# IMU.net
KiCad netlist of a schematic drawn in EAGLE
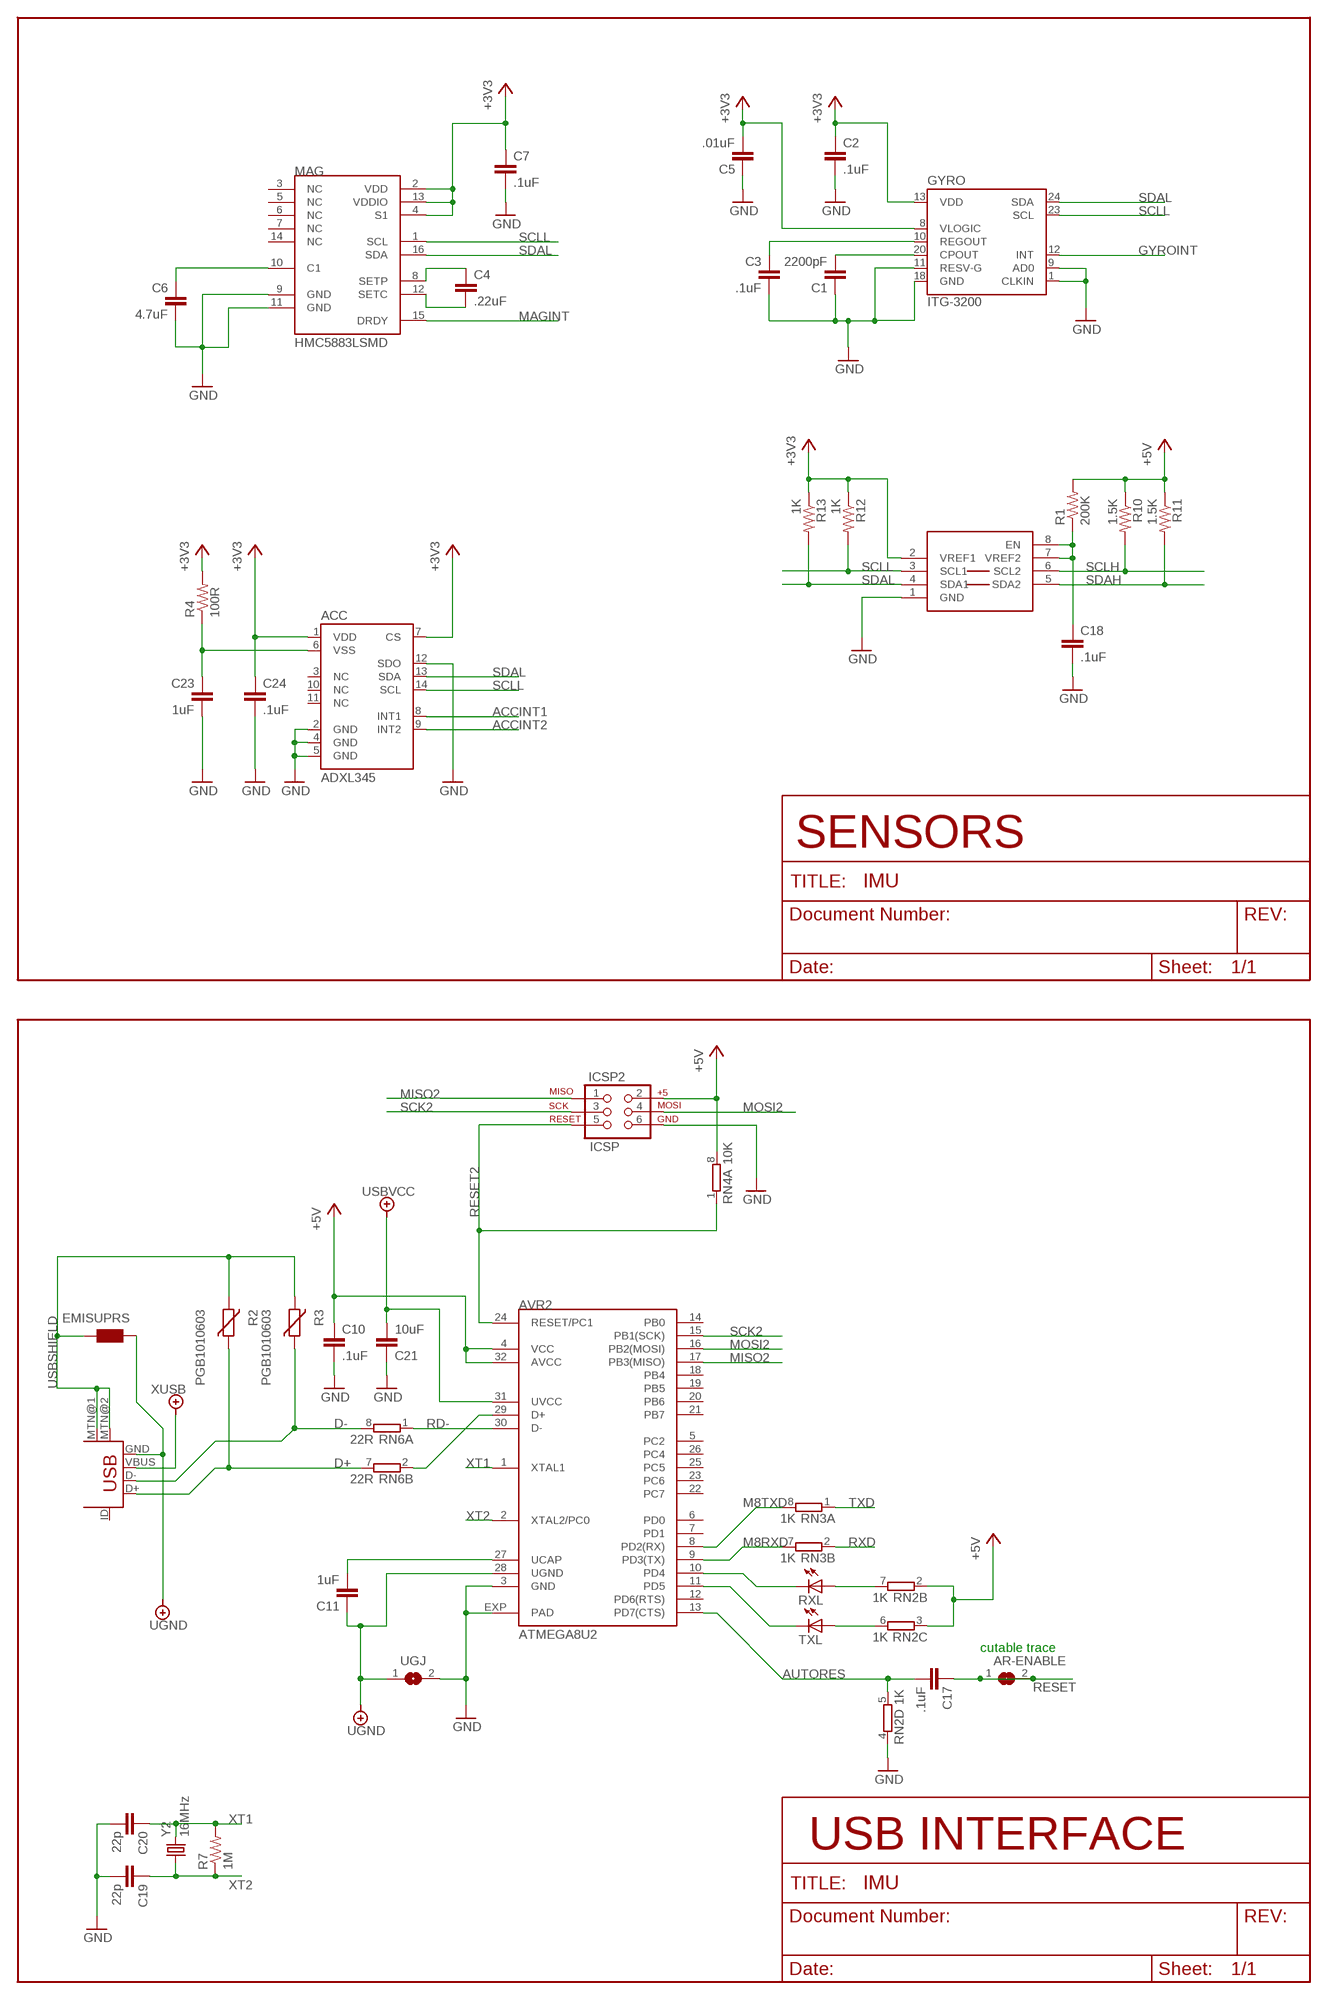
[diagram p0: schematic, sheet 1, part 1 of 2]
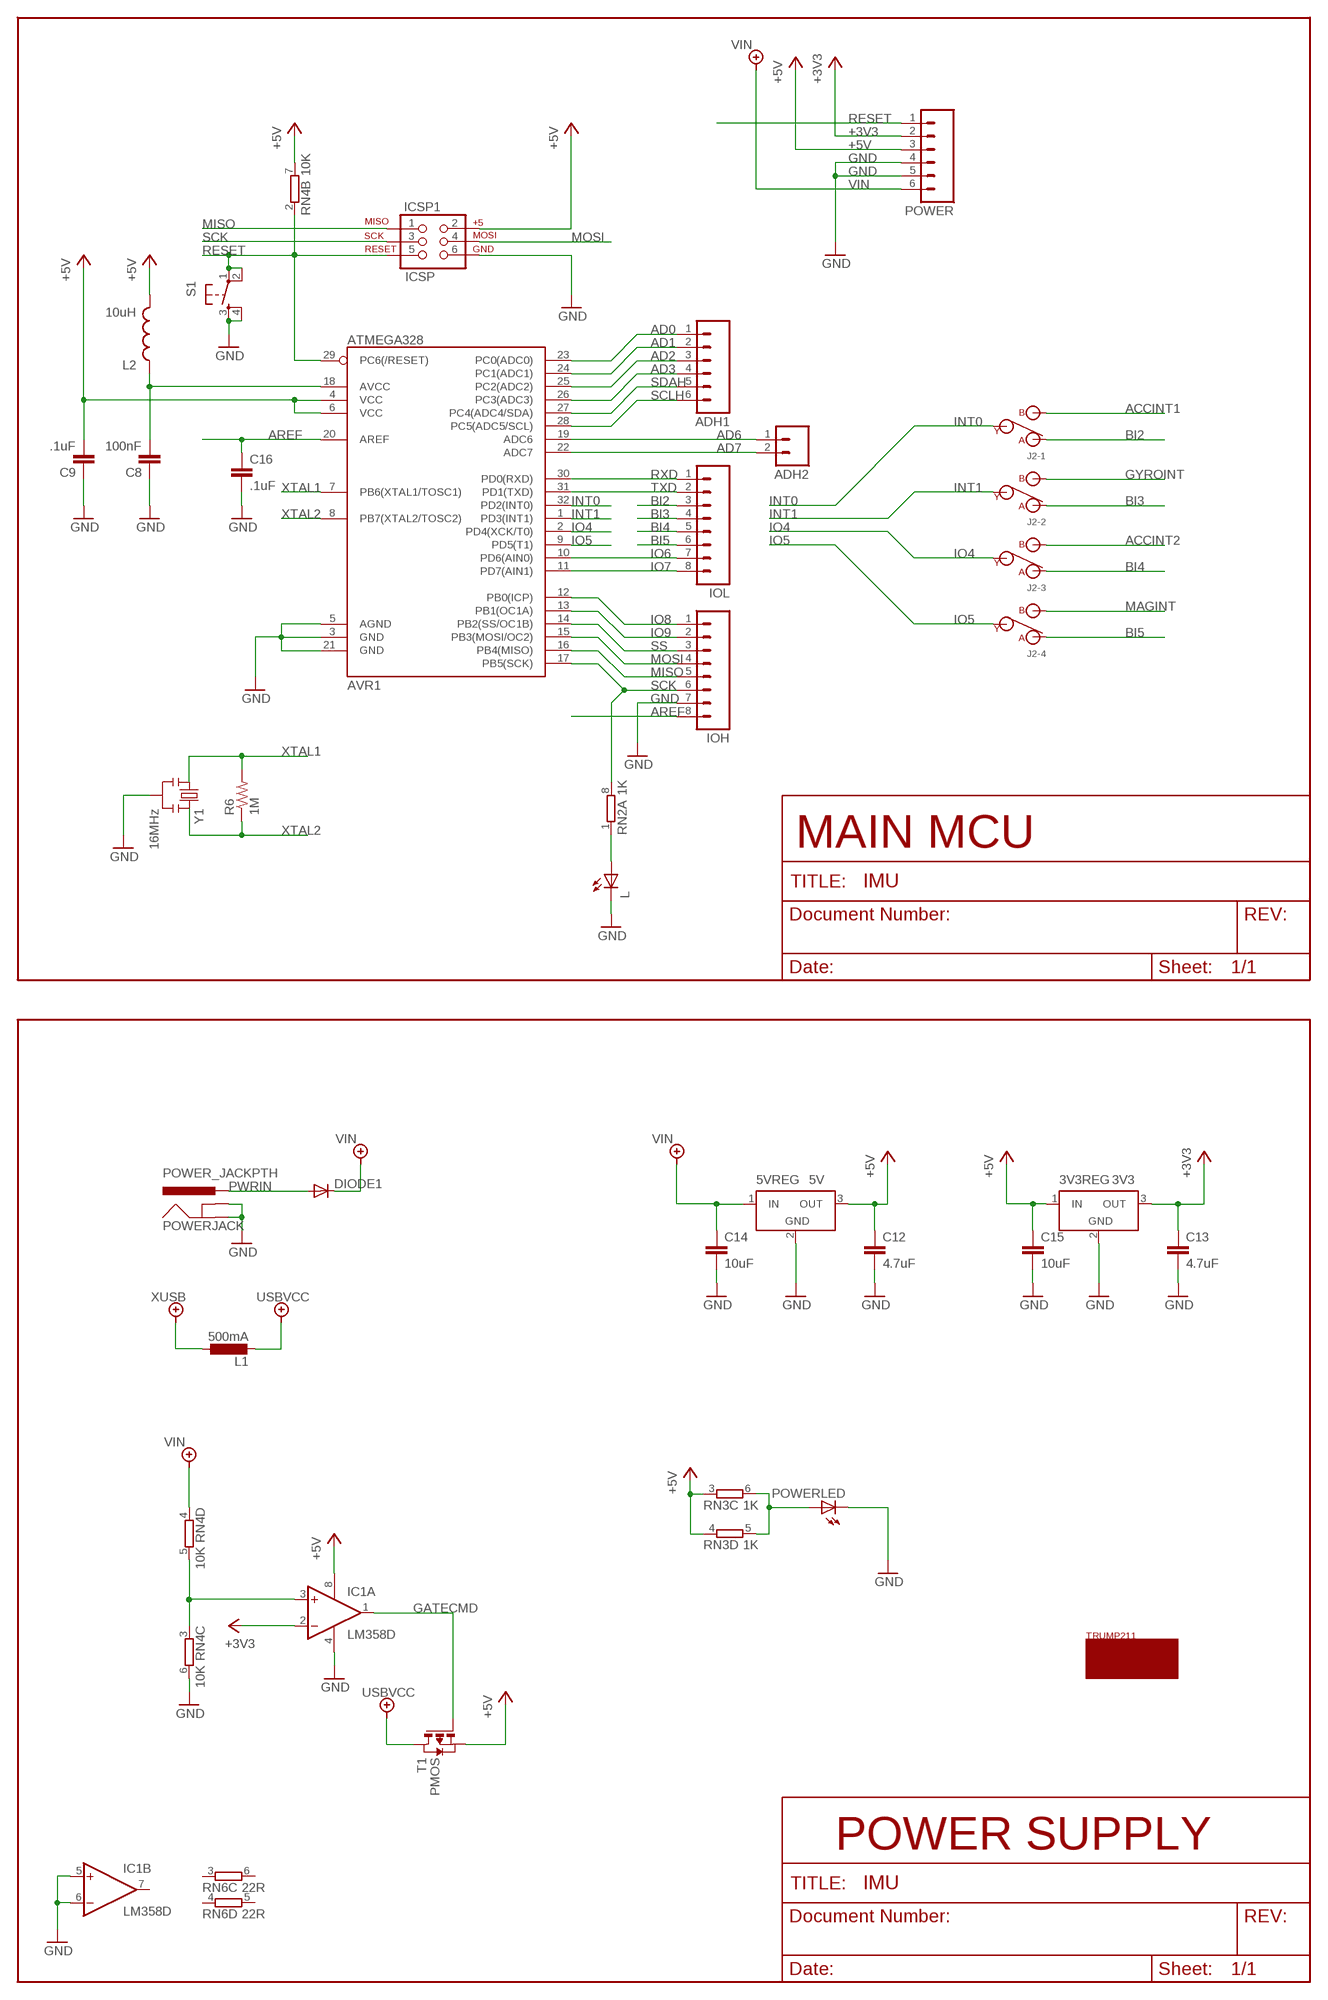
[diagram p1: schematic, sheet 1, part 2 of 2]

(export (version "E")
  (design (tool "Eeschema 10.0.6"))
  (components
    (comp (ref "3V3REG")
      (value "3V3")
      (footprint "eagle-import:SOT223")
      (fields (field (name "MPN") "LT1129CST-5#PBF"))
      (libsource (lib "eagle-import") (part "LT1129CST5"))
    )
    (comp (ref "5VREG")
      (value "5V")
      (footprint "eagle-import:SOT223")
      (fields (field (name "MPN") "LT1129CST-5#PBF"))
      (libsource (lib "eagle-import") (part "LT1129CST5"))
    )
    (comp (ref "ACC")
      (value "ADXL345")
      (footprint "eagle-import:LGA14")
      (libsource (lib "eagle-import") (part "ADXL345"))
    )
    (comp (ref "ADH1")
      (value "M06LOCK")
      (footprint "eagle-import:1X06_LOCK")
      (libsource (lib "eagle-import") (part "M06LOCK"))
    )
    (comp (ref "ADH2")
      (value "M02LOCK")
      (footprint "eagle-import:1X02_LOCK")
      (libsource (lib "eagle-import") (part "M02LOCK"))
    )
    (comp (ref "AR-ENABLE")
      (value "SJ")
      (footprint "eagle-import:SJ")
      (libsource (lib "eagle-import") (part "SJ"))
    )
    (comp (ref "AVR1")
      (value "ATMEGA328")
      (footprint "eagle-import:TQFP32-08")
      (libsource (lib "eagle-import") (part "ATMEGA168"))
    )
    (comp (ref "AVR2")
      (value "ATMEGA8U2")
      (footprint "eagle-import:QFN32")
      (libsource (lib "eagle-import") (part "ATMEGA8U2"))
    )
    (comp (ref "C1")
      (value "2200pF")
      (footprint "eagle-import:C0603")
      (libsource (lib "eagle-import") (part "C-EUC0603"))
    )
    (comp (ref "C2")
      (value ".1uF")
      (footprint "eagle-import:C0603")
      (libsource (lib "eagle-import") (part "C-EUC0603"))
    )
    (comp (ref "C3")
      (value ".1uF")
      (footprint "eagle-import:C0603")
      (libsource (lib "eagle-import") (part "C-EUC0603"))
    )
    (comp (ref "C4")
      (value ".22uF")
      (footprint "eagle-import:C0805")
      (libsource (lib "eagle-import") (part "C-EUC0805"))
    )
    (comp (ref "C5")
      (value ".01uF")
      (footprint "eagle-import:C0603")
      (libsource (lib "eagle-import") (part "C-EUC0603"))
    )
    (comp (ref "C6")
      (value "4.7uF")
      (footprint "eagle-import:C0805")
      (libsource (lib "eagle-import") (part "C-EUC0805"))
    )
    (comp (ref "C7")
      (value ".1uF")
      (footprint "eagle-import:C0603")
      (libsource (lib "eagle-import") (part "C-EUC0603"))
    )
    (comp (ref "C8")
      (value "100nF")
      (footprint "eagle-import:C0603")
      (libsource (lib "eagle-import") (part "C-EUC0603"))
    )
    (comp (ref "C9")
      (value ".1uF")
      (footprint "eagle-import:C0603")
      (libsource (lib "eagle-import") (part "C-EUC0603"))
    )
    (comp (ref "C10")
      (value ".1uF")
      (footprint "eagle-import:C0603")
      (libsource (lib "eagle-import") (part "C-EUC0603"))
    )
    (comp (ref "C11")
      (value "1uF")
      (footprint "eagle-import:C0603")
      (libsource (lib "eagle-import") (part "C-EUC0603"))
    )
    (comp (ref "C12")
      (value "4.7uF")
      (footprint "eagle-import:C1206")
      (libsource (lib "eagle-import") (part "C-EUC1206"))
    )
    (comp (ref "C13")
      (value "4.7uF")
      (footprint "eagle-import:C1206")
      (libsource (lib "eagle-import") (part "C-EUC1206"))
    )
    (comp (ref "C14")
      (value "10uF")
      (footprint "eagle-import:C1206")
      (libsource (lib "eagle-import") (part "C-EUC1206"))
    )
    (comp (ref "C15")
      (value "10uF")
      (footprint "eagle-import:C1206")
      (libsource (lib "eagle-import") (part "C-EUC1206"))
    )
    (comp (ref "C16")
      (value ".1uF")
      (footprint "eagle-import:C0603")
      (libsource (lib "eagle-import") (part "C-EUC0603"))
    )
    (comp (ref "C17")
      (value ".1uF")
      (footprint "eagle-import:C0603")
      (libsource (lib "eagle-import") (part "C-EUC0603"))
    )
    (comp (ref "C18")
      (value ".1uF")
      (footprint "eagle-import:C0603")
      (libsource (lib "eagle-import") (part "C-EUC0603"))
    )
    (comp (ref "C19")
      (value "22p")
      (footprint "eagle-import:C0603")
      (libsource (lib "eagle-import") (part "C-EUC0603"))
    )
    (comp (ref "C20")
      (value "22p")
      (footprint "eagle-import:C0603")
      (libsource (lib "eagle-import") (part "C-EUC0603"))
    )
    (comp (ref "C21")
      (value "10uF")
      (footprint "eagle-import:C0805")
      (libsource (lib "eagle-import") (part "C-EUC0805"))
    )
    (comp (ref "C23")
      (value "1uF")
      (footprint "eagle-import:C0805")
      (libsource (lib "eagle-import") (part "C-EUC0805"))
    )
    (comp (ref "C24")
      (value ".1uF")
      (footprint "eagle-import:C0603")
      (libsource (lib "eagle-import") (part "C-EUC0603"))
    )
    (comp (ref "DIODE1")
      (value "DIODESMA")
      (footprint "eagle-import:SMA-DIODE")
      (libsource (lib "eagle-import") (part "DIODESMA"))
    )
    (comp (ref "EMISUPRS")
      (value "WE-CBF_0805")
      (footprint "eagle-import:0805")
      (libsource (lib "eagle-import") (part "WE-CBF_0805"))
    )
    (comp (ref "GYRO")
      (value "ITG-3200")
      (footprint "eagle-import:QFN-24")
      (libsource (lib "eagle-import") (part "ITG-3200"))
    )
    (comp (ref "IC1")
      (value "LM358D")
      (footprint "eagle-import:SO08")
      (libsource (lib "eagle-import") (part "LM358D"))
    )
    (comp (ref "ICSP1")
      (value "ICSP")
      (footprint "eagle-import:2X3_LOCK")
      (libsource (lib "eagle-import") (part "AVR_SPI_PRG_62X3_LOCK"))
    )
    (comp (ref "ICSP2")
      (value "ICSP")
      (footprint "eagle-import:2X3_LOCK")
      (libsource (lib "eagle-import") (part "AVR_SPI_PRG_62X3_LOCK"))
    )
    (comp (ref "IOH")
      (value "M08LOCK")
      (footprint "eagle-import:1X08_LOCK")
      (libsource (lib "eagle-import") (part "M08LOCK"))
    )
    (comp (ref "IOL")
      (value "M08LOCK")
      (footprint "eagle-import:1X08_LOCK")
      (libsource (lib "eagle-import") (part "M08LOCK"))
    )
    (comp (ref "J2")
      (value "4POS_SPDT_DIP")
      (footprint "eagle-import:4X3_JUMP")
      (libsource (lib "eagle-import") (part "4POS_SPDT_DIP"))
    )
    (comp (ref "L")
      (value "LEDCHIP-LED0805")
      (footprint "eagle-import:CHIP-LED0805")
      (libsource (lib "eagle-import") (part "LEDCHIP-LED0805"))
    )
    (comp (ref "L1")
      (value "500mA")
      (footprint "eagle-import:L1812")
      (libsource (lib "eagle-import") (part "L-EUL1812"))
    )
    (comp (ref "L2")
      (value "10uH")
      (footprint "eagle-import:0805")
      (libsource (lib "eagle-import") (part "INDUCTOR0805"))
    )
    (comp (ref "MAG")
      (value "HMC5883LSMD")
      (footprint "eagle-import:16LPCC")
      (libsource (lib "eagle-import") (part "HMC5883LSMD"))
    )
    (comp (ref "MINIUSB")
      (value "USBMINI")
      (footprint "eagle-import:USBMINI")
      (libsource (lib "eagle-import") (part "USBMINI"))
    )
    (comp (ref "POWER")
      (value "M06LOCK")
      (footprint "eagle-import:1X06_LOCK")
      (libsource (lib "eagle-import") (part "M06LOCK"))
    )
    (comp (ref "POWERJACK")
      (value "POWER_JACKPTH")
      (footprint "eagle-import:POWER_JACK_PTH")
      (libsource (lib "eagle-import") (part "POWER_JACKPTH"))
    )
    (comp (ref "POWERLED")
      (value "LEDCHIP-LED0805")
      (footprint "eagle-import:CHIP-LED0805")
      (libsource (lib "eagle-import") (part "LEDCHIP-LED0805"))
    )
    (comp (ref "R1")
      (value "200K")
      (footprint "eagle-import:R0603")
      (libsource (lib "eagle-import") (part "R-US_R0603"))
    )
    (comp (ref "R2")
      (value "PGB1010603")
      (footprint "eagle-import:CT_CN0603")
      (libsource (lib "eagle-import") (part "VARISTORCN0603"))
    )
    (comp (ref "R3")
      (value "PGB1010603")
      (footprint "eagle-import:CT_CN0603")
      (libsource (lib "eagle-import") (part "VARISTORCN0603"))
    )
    (comp (ref "R4")
      (value "100R")
      (footprint "eagle-import:R0603")
      (libsource (lib "eagle-import") (part "R-US_R0603"))
    )
    (comp (ref "R6")
      (value "1M")
      (footprint "eagle-import:R0603")
      (libsource (lib "eagle-import") (part "R-US_R0603"))
    )
    (comp (ref "R7")
      (value "1M")
      (footprint "eagle-import:R0603")
      (libsource (lib "eagle-import") (part "R-US_R0603"))
    )
    (comp (ref "R10")
      (value "1.5K")
      (footprint "eagle-import:R0603")
      (libsource (lib "eagle-import") (part "R-US_R0603"))
    )
    (comp (ref "R11")
      (value "1.5K")
      (footprint "eagle-import:R0603")
      (libsource (lib "eagle-import") (part "R-US_R0603"))
    )
    (comp (ref "R12")
      (value "1K")
      (footprint "eagle-import:R0603")
      (libsource (lib "eagle-import") (part "R-US_R0603"))
    )
    (comp (ref "R13")
      (value "1K")
      (footprint "eagle-import:R0603")
      (libsource (lib "eagle-import") (part "R-US_R0603"))
    )
    (comp (ref "RN2")
      (value "1K")
      (footprint "eagle-import:CAY16")
      (libsource (lib "eagle-import") (part "4R-NCAY16"))
    )
    (comp (ref "RN3")
      (value "1K")
      (footprint "eagle-import:CAY16")
      (libsource (lib "eagle-import") (part "4R-NCAY16"))
    )
    (comp (ref "RN4")
      (value "10K")
      (footprint "eagle-import:CAY16")
      (libsource (lib "eagle-import") (part "4R-NCAY16"))
    )
    (comp (ref "RN6")
      (value "22R")
      (footprint "eagle-import:CAY16")
      (libsource (lib "eagle-import") (part "4R-NCAY16"))
    )
    (comp (ref "RXL")
      (value "LEDCHIP-LED0805")
      (footprint "eagle-import:CHIP-LED0805")
      (libsource (lib "eagle-import") (part "LEDCHIP-LED0805"))
    )
    (comp (ref "S1")
      (value "TAC_SWITCHSMD")
      (footprint "eagle-import:TACTILE_SWITCH_SMD")
      (libsource (lib "eagle-import") (part "TAC_SWITCHSMD"))
    )
    (comp (ref "T1")
      (value "PMOS")
      (footprint "eagle-import:SOT-23")
      (libsource (lib "eagle-import") (part "PMOSSOT23"))
    )
    (comp (ref "TRANSLATOR")
      (value "PCA9306")
      (footprint "eagle-import:PSOP-8")
      (libsource (lib "eagle-import") (part "PCA9306"))
    )
    (comp (ref "TXL")
      (value "LEDCHIP-LED0805")
      (footprint "eagle-import:CHIP-LED0805")
      (libsource (lib "eagle-import") (part "LEDCHIP-LED0805"))
    )
    (comp (ref "U$1")
      (value "TRUMPLOGO")
      (footprint "eagle-import:TRUMPLOGO")
      (libsource (lib "eagle-import") (part "TRUMPLOGO"))
    )
    (comp (ref "UGJ") (value "SJ") (footprint "eagle-import:SJ") (libsource (lib "eagle-import") (part "SJ")))
    (comp (ref "Y1")
      (value "16MHz")
      (footprint "eagle-import:RESONATOR-SMD")
      (libsource (lib "eagle-import") (part "RESONATORSMD"))
    )
    (comp (ref "Y2")
      (value "16MHz")
      (footprint "eagle-import:CRYSTALSMD")
      (libsource (lib "eagle-import") (part "CRYSTAL"))
    )
  )
  (nets
    (net (code "1") (name "+3V3") (class "Default")
      (node (ref "3V3REG") (pin "3") (pinfunction "OUT_3") (pintype "output"))
      (node (ref "ACC") (pin "1") (pinfunction "VDD_1") (pintype "bidirectional"))
      (node (ref "ACC") (pin "7") (pinfunction "CS_7") (pintype "bidirectional"))
      (node (ref "C13") (pin "1") (pinfunction "1_1") (pintype "passive"))
      (node (ref "C2") (pin "1") (pinfunction "1_1") (pintype "passive"))
      (node (ref "C24") (pin "1") (pinfunction "1_1") (pintype "passive"))
      (node (ref "C5") (pin "2") (pinfunction "2_2") (pintype "passive"))
      (node (ref "C7") (pin "1") (pinfunction "1_1") (pintype "passive"))
      (node (ref "GYRO") (pin "13") (pinfunction "VDD_13") (pintype "bidirectional"))
      (node (ref "GYRO") (pin "8") (pinfunction "VLOGIC_8") (pintype "bidirectional"))
      (node (ref "IC1") (pin "2") (pinfunction "-IN_2") (pintype "input"))
      (node (ref "MAG") (pin "13") (pinfunction "VDDIO_13") (pintype "bidirectional"))
      (node (ref "MAG") (pin "2") (pinfunction "VDD_2") (pintype "bidirectional"))
      (node (ref "MAG") (pin "4") (pinfunction "S1_4") (pintype "bidirectional"))
      (node (ref "POWER") (pin "2") (pinfunction "2_2") (pintype "passive"))
      (node (ref "R12") (pin "1") (pinfunction "1_1") (pintype "passive"))
      (node (ref "R13") (pin "1") (pinfunction "1_1") (pintype "passive"))
      (node (ref "R4") (pin "2") (pinfunction "2_2") (pintype "passive"))
      (node (ref "TRANSLATOR") (pin "2") (pinfunction "VREF1_2") (pintype "bidirectional"))
    )
    (net (code "2") (name "+5V") (class "Default")
      (node (ref "3V3REG") (pin "1") (pinfunction "IN_1") (pintype "input"))
      (node (ref "5VREG") (pin "3") (pinfunction "OUT_3") (pintype "output"))
      (node (ref "AVR1") (pin "4") (pinfunction "VCC_4") (pintype "bidirectional"))
      (node (ref "AVR1") (pin "6") (pinfunction "VCC_6") (pintype "bidirectional"))
      (node (ref "AVR2") (pin "32") (pinfunction "AVCC_32") (pintype "bidirectional"))
      (node (ref "AVR2") (pin "4") (pinfunction "VCC_4") (pintype "bidirectional"))
      (node (ref "C10") (pin "1") (pinfunction "1_1") (pintype "passive"))
      (node (ref "C12") (pin "1") (pinfunction "1_1") (pintype "passive"))
      (node (ref "C15") (pin "1") (pinfunction "1_1") (pintype "passive"))
      (node (ref "C9") (pin "2") (pinfunction "2_2") (pintype "passive"))
      (node (ref "IC1") (pin "8") (pinfunction "V+_8") (pintype "power_in"))
      (node (ref "ICSP1") (pin "2") (pinfunction "2_2") (pintype "passive"))
      (node (ref "ICSP2") (pin "2") (pinfunction "2_2") (pintype "passive"))
      (node (ref "L2") (pin "2") (pinfunction "2_2") (pintype "passive"))
      (node (ref "POWER") (pin "3") (pinfunction "3_3") (pintype "passive"))
      (node (ref "R1") (pin "2") (pinfunction "2_2") (pintype "passive"))
      (node (ref "R10") (pin "1") (pinfunction "1_1") (pintype "passive"))
      (node (ref "R11") (pin "1") (pinfunction "1_1") (pintype "passive"))
      (node (ref "RN2") (pin "2") (pinfunction "1_2") (pintype "passive"))
      (node (ref "RN2") (pin "3") (pinfunction "1_3") (pintype "passive"))
      (node (ref "RN3") (pin "3") (pinfunction "1_3") (pintype "passive"))
      (node (ref "RN3") (pin "4") (pinfunction "1_4") (pintype "passive"))
      (node (ref "RN4") (pin "7") (pinfunction "2_7") (pintype "passive"))
      (node (ref "RN4") (pin "8") (pinfunction "2_8") (pintype "passive"))
      (node (ref "T1") (pin "2") (pinfunction "S_2") (pintype "passive"))
    )
    (net (code "3") (name "/ACCINT1") (class "Default")
      (node (ref "ACC") (pin "8") (pinfunction "INT1_8") (pintype "bidirectional"))
      (node (ref "J2") (pin "R1") (pinfunction "B_R1") (pintype "bidirectional"))
    )
    (net (code "4") (name "/ACCINT2") (class "Default")
      (node (ref "ACC") (pin "9") (pinfunction "INT2_9") (pintype "bidirectional"))
      (node (ref "J2") (pin "R3") (pinfunction "B_R3") (pintype "bidirectional"))
    )
    (net (code "5") (name "/AD0") (class "Default")
      (node (ref "ADH1") (pin "1") (pinfunction "1_1") (pintype "passive"))
      (node (ref "AVR1") (pin "23") (pinfunction "PC0(ADC0)_23") (pintype "bidirectional"))
    )
    (net (code "6") (name "/AD1") (class "Default")
      (node (ref "ADH1") (pin "2") (pinfunction "2_2") (pintype "passive"))
      (node (ref "AVR1") (pin "24") (pinfunction "PC1(ADC1)_24") (pintype "bidirectional"))
    )
    (net (code "7") (name "/AD2") (class "Default")
      (node (ref "ADH1") (pin "3") (pinfunction "3_3") (pintype "passive"))
      (node (ref "AVR1") (pin "25") (pinfunction "PC2(ADC2)_25") (pintype "bidirectional"))
    )
    (net (code "8") (name "/AD3") (class "Default")
      (node (ref "ADH1") (pin "4") (pinfunction "4_4") (pintype "passive"))
      (node (ref "AVR1") (pin "26") (pinfunction "PC3(ADC3)_26") (pintype "bidirectional"))
    )
    (net (code "9") (name "/AD6") (class "Default")
      (node (ref "ADH2") (pin "1") (pinfunction "1_1") (pintype "passive"))
      (node (ref "AVR1") (pin "19") (pinfunction "ADC6_19") (pintype "bidirectional"))
    )
    (net (code "10") (name "/AD7") (class "Default")
      (node (ref "ADH2") (pin "2") (pinfunction "2_2") (pintype "passive"))
      (node (ref "AVR1") (pin "22") (pinfunction "ADC7_22") (pintype "bidirectional"))
    )
    (net (code "11") (name "/AREF") (class "Default")
      (node (ref "AVR1") (pin "20") (pinfunction "AREF_20") (pintype "bidirectional"))
      (node (ref "C16") (pin "1") (pinfunction "1_1") (pintype "passive"))
      (node (ref "IOH") (pin "8") (pinfunction "8_8") (pintype "passive"))
    )
    (net (code "12") (name "/AUTORES") (class "Default")
      (node (ref "AVR2") (pin "13") (pinfunction "PD7(CTS)_13") (pintype "bidirectional"))
      (node (ref "C17") (pin "2") (pinfunction "2_2") (pintype "passive"))
      (node (ref "RN2") (pin "5") (pinfunction "2_5") (pintype "passive"))
    )
    (net (code "13") (name "/BI2") (class "Default")
      (node (ref "IOL") (pin "3") (pinfunction "3_3") (pintype "passive"))
      (node (ref "J2") (pin "L1") (pinfunction "A_L1") (pintype "bidirectional"))
    )
    (net (code "14") (name "/BI3") (class "Default")
      (node (ref "IOL") (pin "4") (pinfunction "4_4") (pintype "passive"))
      (node (ref "J2") (pin "L2") (pinfunction "A_L2") (pintype "bidirectional"))
    )
    (net (code "15") (name "/BI4") (class "Default")
      (node (ref "IOL") (pin "5") (pinfunction "5_5") (pintype "passive"))
      (node (ref "J2") (pin "L3") (pinfunction "A_L3") (pintype "bidirectional"))
    )
    (net (code "16") (name "/BI5") (class "Default")
      (node (ref "IOL") (pin "6") (pinfunction "6_6") (pintype "passive"))
      (node (ref "J2") (pin "L4") (pinfunction "A_L4") (pintype "bidirectional"))
    )
    (net (code "17") (name "/D+") (class "Default")
      (node (ref "MINIUSB") (pin "D+") (pinfunction "D+_D+") (pintype "bidirectional"))
      (node (ref "R2") (pin "1") (pinfunction "1_1") (pintype "passive"))
      (node (ref "RN6") (pin "7") (pinfunction "2_7") (pintype "passive"))
    )
    (net (code "18") (name "/D-") (class "Default")
      (node (ref "MINIUSB") (pin "D-") (pinfunction "D-_D-") (pintype "bidirectional"))
      (node (ref "R3") (pin "1") (pinfunction "1_1") (pintype "passive"))
      (node (ref "RN6") (pin "8") (pinfunction "2_8") (pintype "passive"))
    )
    (net (code "19") (name "/GATECMD") (class "Default")
      (node (ref "IC1") (pin "1") (pinfunction "OUT_1") (pintype "output"))
      (node (ref "T1") (pin "3") (pinfunction "G_3") (pintype "passive"))
    )
    (net (code "20") (name "/GYROINT") (class "Default")
      (node (ref "GYRO") (pin "12") (pinfunction "INT_12") (pintype "bidirectional"))
      (node (ref "J2") (pin "R2") (pinfunction "B_R2") (pintype "bidirectional"))
    )
    (net (code "21") (name "/INT0") (class "Default")
      (node (ref "AVR1") (pin "32") (pinfunction "PD2(INT0)_32") (pintype "bidirectional"))
      (node (ref "J2") (pin "M1") (pinfunction "Y_M1") (pintype "bidirectional"))
    )
    (net (code "22") (name "/INT1") (class "Default")
      (node (ref "AVR1") (pin "1") (pinfunction "PD3(INT1)_1") (pintype "bidirectional"))
      (node (ref "J2") (pin "M2") (pinfunction "Y_M2") (pintype "bidirectional"))
    )
    (net (code "23") (name "/IO4") (class "Default")
      (node (ref "AVR1") (pin "2") (pinfunction "PD4(XCK/T0)_2") (pintype "bidirectional"))
      (node (ref "J2") (pin "M3") (pinfunction "Y_M3") (pintype "bidirectional"))
    )
    (net (code "24") (name "/IO5") (class "Default")
      (node (ref "AVR1") (pin "9") (pinfunction "PD5(T1)_9") (pintype "bidirectional"))
      (node (ref "J2") (pin "M4") (pinfunction "Y_M4") (pintype "bidirectional"))
    )
    (net (code "25") (name "/IO6") (class "Default")
      (node (ref "AVR1") (pin "10") (pinfunction "PD6(AIN0)_10") (pintype "bidirectional"))
      (node (ref "IOL") (pin "7") (pinfunction "7_7") (pintype "passive"))
    )
    (net (code "26") (name "/IO7") (class "Default")
      (node (ref "AVR1") (pin "11") (pinfunction "PD7(AIN1)_11") (pintype "bidirectional"))
      (node (ref "IOL") (pin "8") (pinfunction "8_8") (pintype "passive"))
    )
    (net (code "27") (name "/IO8") (class "Default")
      (node (ref "AVR1") (pin "12") (pinfunction "PB0(ICP)_12") (pintype "bidirectional"))
      (node (ref "IOH") (pin "1") (pinfunction "1_1") (pintype "passive"))
    )
    (net (code "28") (name "/IO9") (class "Default")
      (node (ref "AVR1") (pin "13") (pinfunction "PB1(OC1A)_13") (pintype "bidirectional"))
      (node (ref "IOH") (pin "2") (pinfunction "2_2") (pintype "passive"))
    )
    (net (code "29") (name "/M8RXD") (class "Default")
      (node (ref "AVR2") (pin "9") (pinfunction "PD3(TX)_9") (pintype "bidirectional"))
      (node (ref "RN3") (pin "7") (pinfunction "2_7") (pintype "passive"))
    )
    (net (code "30") (name "/M8TXD") (class "Default")
      (node (ref "AVR2") (pin "8") (pinfunction "PD2(RX)_8") (pintype "bidirectional"))
      (node (ref "RN3") (pin "8") (pinfunction "2_8") (pintype "passive"))
    )
    (net (code "31") (name "/MAGINT") (class "Default")
      (node (ref "J2") (pin "R4") (pinfunction "B_R4") (pintype "bidirectional"))
      (node (ref "MAG") (pin "15") (pinfunction "DRDY_15") (pintype "bidirectional"))
    )
    (net (code "32") (name "/MISO") (class "Default")
      (node (ref "AVR1") (pin "16") (pinfunction "PB4(MISO)_16") (pintype "bidirectional"))
      (node (ref "ICSP1") (pin "1") (pinfunction "1_1") (pintype "passive"))
      (node (ref "IOH") (pin "5") (pinfunction "5_5") (pintype "passive"))
    )
    (net (code "33") (name "/MISO2") (class "Default")
      (node (ref "AVR2") (pin "17") (pinfunction "PB3(MISO)_17") (pintype "bidirectional"))
      (node (ref "ICSP2") (pin "1") (pinfunction "1_1") (pintype "passive"))
    )
    (net (code "34") (name "/MOSI") (class "Default")
      (node (ref "AVR1") (pin "15") (pinfunction "PB3(MOSI/OC2)_15") (pintype "bidirectional"))
      (node (ref "ICSP1") (pin "4") (pinfunction "4_4") (pintype "passive"))
      (node (ref "IOH") (pin "4") (pinfunction "4_4") (pintype "passive"))
    )
    (net (code "35") (name "/MOSI2") (class "Default")
      (node (ref "AVR2") (pin "16") (pinfunction "PB2(MOSI)_16") (pintype "bidirectional"))
      (node (ref "ICSP2") (pin "4") (pinfunction "4_4") (pintype "passive"))
    )
    (net (code "36") (name "/PWRIN") (class "Default")
      (node (ref "DIODE1") (pin "A") (pinfunction "A_A") (pintype "passive"))
      (node (ref "POWERJACK") (pin "PWR") (pinfunction "PWR_PWR") (pintype "bidirectional"))
    )
    (net (code "37") (name "/RD-") (class "Default")
      (node (ref "AVR2") (pin "30") (pinfunction "D-_30") (pintype "bidirectional"))
      (node (ref "RN6") (pin "1") (pinfunction "1_1") (pintype "passive"))
    )
    (net (code "38") (name "/RESET") (class "Default")
      (node (ref "AR-ENABLE") (pin "1") (pinfunction "1_1") (pintype "passive"))
      (node (ref "AR-ENABLE") (pin "2") (pinfunction "2_2") (pintype "passive"))
      (node (ref "AVR1") (pin "29") (pinfunction "PC6(/RESET)_29") (pintype "bidirectional"))
      (node (ref "C17") (pin "1") (pinfunction "1_1") (pintype "passive"))
      (node (ref "ICSP1") (pin "5") (pinfunction "5_5") (pintype "passive"))
      (node (ref "POWER") (pin "1") (pinfunction "1_1") (pintype "passive"))
      (node (ref "RN4") (pin "2") (pinfunction "1_2") (pintype "passive"))
      (node (ref "S1") (pin "1") (pinfunction "1_1") (pintype "passive"))
      (node (ref "S1") (pin "2") (pinfunction "2_2") (pintype "passive"))
    )
    (net (code "39") (name "/RESET2") (class "Default")
      (node (ref "AVR2") (pin "24") (pinfunction "RESET/PC1_24") (pintype "bidirectional"))
      (node (ref "ICSP2") (pin "5") (pinfunction "5_5") (pintype "passive"))
      (node (ref "RN4") (pin "1") (pinfunction "1_1") (pintype "passive"))
    )
    (net (code "40") (name "/RXD") (class "Default")
      (node (ref "AVR1") (pin "30") (pinfunction "PD0(RXD)_30") (pintype "bidirectional"))
      (node (ref "IOL") (pin "1") (pinfunction "1_1") (pintype "passive"))
      (node (ref "RN3") (pin "2") (pinfunction "1_2") (pintype "passive"))
    )
    (net (code "41") (name "/SCK") (class "Default")
      (node (ref "AVR1") (pin "17") (pinfunction "PB5(SCK)_17") (pintype "bidirectional"))
      (node (ref "ICSP1") (pin "3") (pinfunction "3_3") (pintype "passive"))
      (node (ref "IOH") (pin "6") (pinfunction "6_6") (pintype "passive"))
      (node (ref "RN2") (pin "8") (pinfunction "2_8") (pintype "passive"))
    )
    (net (code "42") (name "/SCK2") (class "Default")
      (node (ref "AVR2") (pin "15") (pinfunction "PB1(SCK)_15") (pintype "bidirectional"))
      (node (ref "ICSP2") (pin "3") (pinfunction "3_3") (pintype "passive"))
    )
    (net (code "43") (name "/SCLH") (class "Default")
      (node (ref "ADH1") (pin "6") (pinfunction "6_6") (pintype "passive"))
      (node (ref "AVR1") (pin "28") (pinfunction "PC5(ADC5/SCL)_28") (pintype "bidirectional"))
      (node (ref "R10") (pin "2") (pinfunction "2_2") (pintype "passive"))
      (node (ref "TRANSLATOR") (pin "6") (pinfunction "SCL2_6") (pintype "bidirectional"))
    )
    (net (code "44") (name "/SCLL") (class "Default")
      (node (ref "ACC") (pin "14") (pinfunction "SCL_14") (pintype "bidirectional"))
      (node (ref "GYRO") (pin "23") (pinfunction "SCL_23") (pintype "bidirectional"))
      (node (ref "MAG") (pin "1") (pinfunction "SCL_1") (pintype "bidirectional"))
      (node (ref "R12") (pin "2") (pinfunction "2_2") (pintype "passive"))
      (node (ref "TRANSLATOR") (pin "3") (pinfunction "SCL1_3") (pintype "bidirectional"))
    )
    (net (code "45") (name "/SDAH") (class "Default")
      (node (ref "ADH1") (pin "5") (pinfunction "5_5") (pintype "passive"))
      (node (ref "AVR1") (pin "27") (pinfunction "PC4(ADC4/SDA)_27") (pintype "bidirectional"))
      (node (ref "R11") (pin "2") (pinfunction "2_2") (pintype "passive"))
      (node (ref "TRANSLATOR") (pin "5") (pinfunction "SDA2_5") (pintype "bidirectional"))
    )
    (net (code "46") (name "/SDAL") (class "Default")
      (node (ref "ACC") (pin "13") (pinfunction "SDA_13") (pintype "bidirectional"))
      (node (ref "GYRO") (pin "24") (pinfunction "SDA_24") (pintype "bidirectional"))
      (node (ref "MAG") (pin "16") (pinfunction "SDA_16") (pintype "bidirectional"))
      (node (ref "R13") (pin "2") (pinfunction "2_2") (pintype "passive"))
      (node (ref "TRANSLATOR") (pin "4") (pinfunction "SDA1_4") (pintype "bidirectional"))
    )
    (net (code "47") (name "/SS") (class "Default")
      (node (ref "AVR1") (pin "14") (pinfunction "PB2(SS/OC1B)_14") (pintype "bidirectional"))
      (node (ref "IOH") (pin "3") (pinfunction "3_3") (pintype "passive"))
    )
    (net (code "48") (name "/TXD") (class "Default")
      (node (ref "AVR1") (pin "31") (pinfunction "PD1(TXD)_31") (pintype "bidirectional"))
      (node (ref "IOL") (pin "2") (pinfunction "2_2") (pintype "passive"))
      (node (ref "RN3") (pin "1") (pinfunction "1_1") (pintype "passive"))
    )
    (net (code "49") (name "/USBSHIELD") (class "Default")
      (node (ref "EMISUPRS") (pin "2") (pinfunction "2_2") (pintype "passive"))
      (node (ref "MINIUSB") (pin "MTN@1") (pinfunction "P$2_MTN@1") (pintype "bidirectional"))
      (node (ref "MINIUSB") (pin "MTN@2") (pinfunction "P$1_MTN@2") (pintype "bidirectional"))
      (node (ref "R2") (pin "2") (pinfunction "2_2") (pintype "passive"))
      (node (ref "R3") (pin "2") (pinfunction "2_2") (pintype "passive"))
    )
    (net (code "50") (name "/XT1") (class "Default")
      (node (ref "AVR2") (pin "1") (pinfunction "XTAL1_1") (pintype "bidirectional"))
      (node (ref "C20") (pin "1") (pinfunction "1_1") (pintype "passive"))
      (node (ref "R7") (pin "2") (pinfunction "2_2") (pintype "passive"))
      (node (ref "Y2") (pin "3") (pinfunction "2_3") (pintype "passive"))
    )
    (net (code "51") (name "/XT2") (class "Default")
      (node (ref "AVR2") (pin "2") (pinfunction "XTAL2/PC0_2") (pintype "bidirectional"))
      (node (ref "C19") (pin "1") (pinfunction "1_1") (pintype "passive"))
      (node (ref "R7") (pin "1") (pinfunction "1_1") (pintype "passive"))
      (node (ref "Y2") (pin "1") (pinfunction "1_1") (pintype "passive"))
    )
    (net (code "52") (name "/XTAL1") (class "Default")
      (node (ref "AVR1") (pin "7") (pinfunction "PB6(XTAL1/TOSC1)_7") (pintype "bidirectional"))
      (node (ref "R6") (pin "2") (pinfunction "2_2") (pintype "passive"))
      (node (ref "Y1") (pin "1") (pinfunction "1_1") (pintype "passive"))
    )
    (net (code "53") (name "/XTAL2") (class "Default")
      (node (ref "AVR1") (pin "8") (pinfunction "PB7(XTAL2/TOSC2)_8") (pintype "bidirectional"))
      (node (ref "R6") (pin "1") (pinfunction "1_1") (pintype "passive"))
      (node (ref "Y1") (pin "3") (pinfunction "3_3") (pintype "passive"))
    )
    (net (code "54") (name "GND") (class "Default")
      (node (ref "3V3REG") (pin "2") (pinfunction "GND_2") (pintype "power_in"))
      (node (ref "5VREG") (pin "2") (pinfunction "GND_2") (pintype "power_in"))
      (node (ref "ACC") (pin "12") (pinfunction "SDO_12") (pintype "bidirectional"))
      (node (ref "ACC") (pin "2") (pinfunction "GND_2") (pintype "bidirectional"))
      (node (ref "ACC") (pin "4") (pinfunction "GND_4") (pintype "bidirectional"))
      (node (ref "ACC") (pin "5") (pinfunction "GND_5") (pintype "bidirectional"))
      (node (ref "AVR1") (pin "21") (pinfunction "GND_21") (pintype "bidirectional"))
      (node (ref "AVR1") (pin "3") (pinfunction "GND_3") (pintype "bidirectional"))
      (node (ref "AVR1") (pin "5") (pinfunction "AGND_5") (pintype "bidirectional"))
      (node (ref "AVR2") (pin "3") (pinfunction "GND_3") (pintype "bidirectional"))
      (node (ref "AVR2") (pin "EXP") (pinfunction "PAD_EXP") (pintype "bidirectional"))
      (node (ref "C1") (pin "1") (pinfunction "1_1") (pintype "passive"))
      (node (ref "C10") (pin "2") (pinfunction "2_2") (pintype "passive"))
      (node (ref "C12") (pin "2") (pinfunction "2_2") (pintype "passive"))
      (node (ref "C13") (pin "2") (pinfunction "2_2") (pintype "passive"))
      (node (ref "C14") (pin "2") (pinfunction "2_2") (pintype "passive"))
      (node (ref "C15") (pin "2") (pinfunction "2_2") (pintype "passive"))
      (node (ref "C16") (pin "2") (pinfunction "2_2") (pintype "passive"))
      (node (ref "C18") (pin "2") (pinfunction "2_2") (pintype "passive"))
      (node (ref "C19") (pin "2") (pinfunction "2_2") (pintype "passive"))
      (node (ref "C2") (pin "2") (pinfunction "2_2") (pintype "passive"))
      (node (ref "C20") (pin "2") (pinfunction "2_2") (pintype "passive"))
      (node (ref "C21") (pin "1") (pinfunction "1_1") (pintype "passive"))
      (node (ref "C23") (pin "2") (pinfunction "2_2") (pintype "passive"))
      (node (ref "C24") (pin "2") (pinfunction "2_2") (pintype "passive"))
      (node (ref "C3") (pin "2") (pinfunction "2_2") (pintype "passive"))
      (node (ref "C5") (pin "1") (pinfunction "1_1") (pintype "passive"))
      (node (ref "C6") (pin "2") (pinfunction "2_2") (pintype "passive"))
      (node (ref "C7") (pin "2") (pinfunction "2_2") (pintype "passive"))
      (node (ref "C8") (pin "1") (pinfunction "1_1") (pintype "passive"))
      (node (ref "C9") (pin "1") (pinfunction "1_1") (pintype "passive"))
      (node (ref "GYRO") (pin "1") (pinfunction "CLKIN_1") (pintype "bidirectional"))
      (node (ref "GYRO") (pin "11") (pinfunction "RESV-G_11") (pintype "bidirectional"))
      (node (ref "GYRO") (pin "18") (pinfunction "GND_18") (pintype "bidirectional"))
      (node (ref "GYRO") (pin "9") (pinfunction "AD0_9") (pintype "bidirectional"))
      (node (ref "IC1") (pin "4") (pinfunction "V-_4") (pintype "power_in"))
      (node (ref "IC1") (pin "5") (pinfunction "+IN_5") (pintype "input"))
      (node (ref "IC1") (pin "6") (pinfunction "-IN_6") (pintype "input"))
      (node (ref "ICSP1") (pin "6") (pinfunction "6_6") (pintype "passive"))
      (node (ref "ICSP2") (pin "6") (pinfunction "6_6") (pintype "passive"))
      (node (ref "IOH") (pin "7") (pinfunction "7_7") (pintype "passive"))
      (node (ref "L") (pin "C") (pinfunction "C_C") (pintype "passive"))
      (node (ref "MAG") (pin "11") (pinfunction "GND_11") (pintype "bidirectional"))
      (node (ref "MAG") (pin "9") (pinfunction "GND_9") (pintype "bidirectional"))
      (node (ref "POWER") (pin "4") (pinfunction "4_4") (pintype "passive"))
      (node (ref "POWER") (pin "5") (pinfunction "5_5") (pintype "passive"))
      (node (ref "POWERJACK") (pin "GND") (pinfunction "GND_GND") (pintype "bidirectional"))
      (node (ref "POWERJACK") (pin "GNDBREAK") (pinfunction "GNDBREAK_GNDBREAK") (pintype "bidirectional"))
      (node (ref "POWERLED") (pin "C") (pinfunction "C_C") (pintype "passive"))
      (node (ref "RN2") (pin "4") (pinfunction "1_4") (pintype "passive"))
      (node (ref "RN4") (pin "6") (pinfunction "2_6") (pintype "passive"))
      (node (ref "S1") (pin "3") (pinfunction "3_3") (pintype "passive"))
      (node (ref "S1") (pin "4") (pinfunction "4_4") (pintype "passive"))
      (node (ref "TRANSLATOR") (pin "1") (pinfunction "GND_1") (pintype "bidirectional"))
      (node (ref "UGJ") (pin "2") (pinfunction "2_2") (pintype "passive"))
      (node (ref "Y1") (pin "2") (pinfunction "2_2") (pintype "passive"))
    )
    (net (code "55") (name "Net-(ACC-VSS)") (class "Default")
      (node (ref "ACC") (pin "6") (pinfunction "VSS_6") (pintype "bidirectional"))
      (node (ref "C23") (pin "1") (pinfunction "1_1") (pintype "passive"))
      (node (ref "R4") (pin "1") (pinfunction "1_1") (pintype "passive"))
    )
    (net (code "56") (name "Net-(AVR1-AVCC)") (class "Default")
      (node (ref "AVR1") (pin "18") (pinfunction "AVCC_18") (pintype "bidirectional"))
      (node (ref "C8") (pin "2") (pinfunction "2_2") (pintype "passive"))
      (node (ref "L2") (pin "1") (pinfunction "1_1") (pintype "passive"))
    )
    (net (code "57") (name "Net-(AVR2-D+)") (class "Default")
      (node (ref "AVR2") (pin "29") (pinfunction "D+_29") (pintype "bidirectional"))
      (node (ref "RN6") (pin "2") (pinfunction "1_2") (pintype "passive"))
    )
    (net (code "58") (name "Net-(AVR2-PD4)") (class "Default")
      (node (ref "AVR2") (pin "10") (pinfunction "PD4_10") (pintype "bidirectional"))
      (node (ref "RXL") (pin "C") (pinfunction "C_C") (pintype "passive"))
    )
    (net (code "59") (name "Net-(AVR2-PD5)") (class "Default")
      (node (ref "AVR2") (pin "11") (pinfunction "PD5_11") (pintype "bidirectional"))
      (node (ref "TXL") (pin "C") (pinfunction "C_C") (pintype "passive"))
    )
    (net (code "60") (name "Net-(AVR2-UCAP)") (class "Default")
      (node (ref "AVR2") (pin "27") (pinfunction "UCAP_27") (pintype "bidirectional"))
      (node (ref "C11") (pin "2") (pinfunction "2_2") (pintype "passive"))
    )
    (net (code "61") (name "Net-(GYRO-CPOUT)") (class "Default")
      (node (ref "C1") (pin "2") (pinfunction "2_2") (pintype "passive"))
      (node (ref "GYRO") (pin "20") (pinfunction "CPOUT_20") (pintype "bidirectional"))
    )
    (net (code "62") (name "Net-(GYRO-REGOUT)") (class "Default")
      (node (ref "C3") (pin "1") (pinfunction "1_1") (pintype "passive"))
      (node (ref "GYRO") (pin "10") (pinfunction "REGOUT_10") (pintype "bidirectional"))
    )
    (net (code "63") (name "Net-(IC1A-+IN)") (class "Default")
      (node (ref "IC1") (pin "3") (pinfunction "+IN_3") (pintype "input"))
      (node (ref "RN4") (pin "3") (pinfunction "1_3") (pintype "passive"))
      (node (ref "RN4") (pin "5") (pinfunction "2_5") (pintype "passive"))
    )
    (net (code "64") (name "Net-(L-PadA)") (class "Default")
      (node (ref "L") (pin "A") (pinfunction "A_A") (pintype "passive"))
      (node (ref "RN2") (pin "1") (pinfunction "1_1") (pintype "passive"))
    )
    (net (code "65") (name "Net-(MAG-C1)") (class "Default")
      (node (ref "C6") (pin "1") (pinfunction "1_1") (pintype "passive"))
      (node (ref "MAG") (pin "10") (pinfunction "C1_10") (pintype "bidirectional"))
    )
    (net (code "66") (name "Net-(MAG-SETC)") (class "Default")
      (node (ref "C4") (pin "2") (pinfunction "2_2") (pintype "passive"))
      (node (ref "MAG") (pin "12") (pinfunction "SETC_12") (pintype "bidirectional"))
    )
    (net (code "67") (name "Net-(MAG-SETP)") (class "Default")
      (node (ref "C4") (pin "1") (pinfunction "1_1") (pintype "passive"))
      (node (ref "MAG") (pin "8") (pinfunction "SETP_8") (pintype "bidirectional"))
    )
    (net (code "68") (name "Net-(RN2B-2)") (class "Default")
      (node (ref "RN2") (pin "7") (pinfunction "2_7") (pintype "passive"))
      (node (ref "RXL") (pin "A") (pinfunction "A_A") (pintype "passive"))
    )
    (net (code "69") (name "Net-(RN2C-2)") (class "Default")
      (node (ref "RN2") (pin "6") (pinfunction "2_6") (pintype "passive"))
      (node (ref "TXL") (pin "A") (pinfunction "A_A") (pintype "passive"))
    )
    (net (code "70") (name "Net-(RN3C-2)") (class "Default")
      (node (ref "POWERLED") (pin "A") (pinfunction "A_A") (pintype "passive"))
      (node (ref "RN3") (pin "5") (pinfunction "2_5") (pintype "passive"))
      (node (ref "RN3") (pin "6") (pinfunction "2_6") (pintype "passive"))
    )
    (net (code "71") (name "Net-(TRANSLATOR-EN)") (class "Default")
      (node (ref "C18") (pin "1") (pinfunction "1_1") (pintype "passive"))
      (node (ref "R1") (pin "1") (pinfunction "1_1") (pintype "passive"))
      (node (ref "TRANSLATOR") (pin "7") (pinfunction "VREF2_7") (pintype "bidirectional"))
      (node (ref "TRANSLATOR") (pin "8") (pinfunction "EN_8") (pintype "bidirectional"))
    )
    (net (code "72") (name "UGND") (class "Default")
      (node (ref "AVR2") (pin "28") (pinfunction "UGND_28") (pintype "bidirectional"))
      (node (ref "C11") (pin "1") (pinfunction "1_1") (pintype "passive"))
      (node (ref "EMISUPRS") (pin "1") (pinfunction "1_1") (pintype "passive"))
      (node (ref "MINIUSB") (pin "GND") (pinfunction "GND_GND") (pintype "bidirectional"))
      (node (ref "UGJ") (pin "1") (pinfunction "1_1") (pintype "passive"))
    )
    (net (code "73") (name "USBVCC") (class "Default")
      (node (ref "AVR2") (pin "31") (pinfunction "UVCC_31") (pintype "bidirectional"))
      (node (ref "C21") (pin "2") (pinfunction "2_2") (pintype "passive"))
      (node (ref "L1") (pin "2") (pinfunction "2_2") (pintype "passive"))
      (node (ref "T1") (pin "1") (pinfunction "D_1") (pintype "passive"))
    )
    (net (code "74") (name "VIN") (class "Default")
      (node (ref "5VREG") (pin "1") (pinfunction "IN_1") (pintype "input"))
      (node (ref "C14") (pin "1") (pinfunction "1_1") (pintype "passive"))
      (node (ref "DIODE1") (pin "C") (pinfunction "C_C") (pintype "passive"))
      (node (ref "POWER") (pin "6") (pinfunction "6_6") (pintype "passive"))
      (node (ref "RN4") (pin "4") (pinfunction "1_4") (pintype "passive"))
    )
    (net (code "75") (name "XUSB") (class "Default")
      (node (ref "L1") (pin "1") (pinfunction "1_1") (pintype "passive"))
      (node (ref "MINIUSB") (pin "VBUS") (pinfunction "VBUS_VBUS") (pintype "bidirectional"))
    )
    (net (code "76") (name "unconnected-(ACC-NC-Pad3)") (class "Default")
      (node (ref "ACC") (pin "3") (pinfunction "NC_3") (pintype "bidirectional"))
    )
    (net (code "77") (name "unconnected-(ACC-NC-Pad10)") (class "Default")
      (node (ref "ACC") (pin "10") (pinfunction "NC_10") (pintype "bidirectional"))
    )
    (net (code "78") (name "unconnected-(ACC-NC-Pad11)") (class "Default")
      (node (ref "ACC") (pin "11") (pinfunction "NC_11") (pintype "bidirectional"))
    )
    (net (code "79") (name "unconnected-(AVR2-PB0-Pad14)") (class "Default")
      (node (ref "AVR2") (pin "14") (pinfunction "PB0_14") (pintype "bidirectional"))
    )
    (net (code "80") (name "unconnected-(AVR2-PB4-Pad18)") (class "Default")
      (node (ref "AVR2") (pin "18") (pinfunction "PB4_18") (pintype "bidirectional"))
    )
    (net (code "81") (name "unconnected-(AVR2-PB5-Pad19)") (class "Default")
      (node (ref "AVR2") (pin "19") (pinfunction "PB5_19") (pintype "bidirectional"))
    )
    (net (code "82") (name "unconnected-(AVR2-PB6-Pad20)") (class "Default")
      (node (ref "AVR2") (pin "20") (pinfunction "PB6_20") (pintype "bidirectional"))
    )
    (net (code "83") (name "unconnected-(AVR2-PB7-Pad21)") (class "Default")
      (node (ref "AVR2") (pin "21") (pinfunction "PB7_21") (pintype "bidirectional"))
    )
    (net (code "84") (name "unconnected-(AVR2-PC2-Pad5)") (class "Default")
      (node (ref "AVR2") (pin "5") (pinfunction "PC2_5") (pintype "bidirectional"))
    )
    (net (code "85") (name "unconnected-(AVR2-PC4-Pad26)") (class "Default")
      (node (ref "AVR2") (pin "26") (pinfunction "PC4_26") (pintype "bidirectional"))
    )
    (net (code "86") (name "unconnected-(AVR2-PC5-Pad25)") (class "Default")
      (node (ref "AVR2") (pin "25") (pinfunction "PC5_25") (pintype "bidirectional"))
    )
    (net (code "87") (name "unconnected-(AVR2-PC6-Pad23)") (class "Default")
      (node (ref "AVR2") (pin "23") (pinfunction "PC6_23") (pintype "bidirectional"))
    )
    (net (code "88") (name "unconnected-(AVR2-PC7-Pad22)") (class "Default")
      (node (ref "AVR2") (pin "22") (pinfunction "PC7_22") (pintype "bidirectional"))
    )
    (net (code "89") (name "unconnected-(AVR2-PD0-Pad6)") (class "Default")
      (node (ref "AVR2") (pin "6") (pinfunction "PD0_6") (pintype "bidirectional"))
    )
    (net (code "90") (name "unconnected-(AVR2-PD1-Pad7)") (class "Default")
      (node (ref "AVR2") (pin "7") (pinfunction "PD1_7") (pintype "bidirectional"))
    )
    (net (code "91") (name "unconnected-(AVR2-PD6(RTS)-Pad12)") (class "Default")
      (node (ref "AVR2") (pin "12") (pinfunction "PD6(RTS)_12") (pintype "bidirectional"))
    )
    (net (code "92") (name "unconnected-(IC1B-OUT-Pad7)") (class "Default")
      (node (ref "IC1") (pin "7") (pinfunction "OUT_7") (pintype "output"))
    )
    (net (code "93") (name "unconnected-(MAG-NC-Pad3)") (class "Default")
      (node (ref "MAG") (pin "3") (pinfunction "NC_3") (pintype "bidirectional"))
    )
    (net (code "94") (name "unconnected-(MAG-NC-Pad5)") (class "Default")
      (node (ref "MAG") (pin "5") (pinfunction "NC_5") (pintype "bidirectional"))
    )
    (net (code "95") (name "unconnected-(MAG-NC-Pad6)") (class "Default")
      (node (ref "MAG") (pin "6") (pinfunction "NC_6") (pintype "bidirectional"))
    )
    (net (code "96") (name "unconnected-(MAG-NC-Pad7)") (class "Default")
      (node (ref "MAG") (pin "7") (pinfunction "NC_7") (pintype "bidirectional"))
    )
    (net (code "97") (name "unconnected-(MAG-NC-Pad14)") (class "Default")
      (node (ref "MAG") (pin "14") (pinfunction "NC_14") (pintype "bidirectional"))
    )
    (net (code "98") (name "unconnected-(MINIUSB-PadID)") (class "Default")
      (node (ref "MINIUSB") (pin "ID") (pinfunction "ID_ID") (pintype "bidirectional"))
    )
    (net (code "99") (name "unconnected-(RN6C-1-Pad3)") (class "Default")
      (node (ref "RN6") (pin "3") (pinfunction "1_3") (pintype "passive"))
    )
    (net (code "100") (name "unconnected-(RN6C-2-Pad6)") (class "Default")
      (node (ref "RN6") (pin "6") (pinfunction "2_6") (pintype "passive"))
    )
    (net (code "101") (name "unconnected-(RN6D-1-Pad4)") (class "Default")
      (node (ref "RN6") (pin "4") (pinfunction "1_4") (pintype "passive"))
    )
    (net (code "102") (name "unconnected-(RN6D-2-Pad5)") (class "Default")
      (node (ref "RN6") (pin "5") (pinfunction "2_5") (pintype "passive"))
    )
  )
)
